# fever_meter_v1.net
KiCad netlist of a schematic drawn in EAGLE
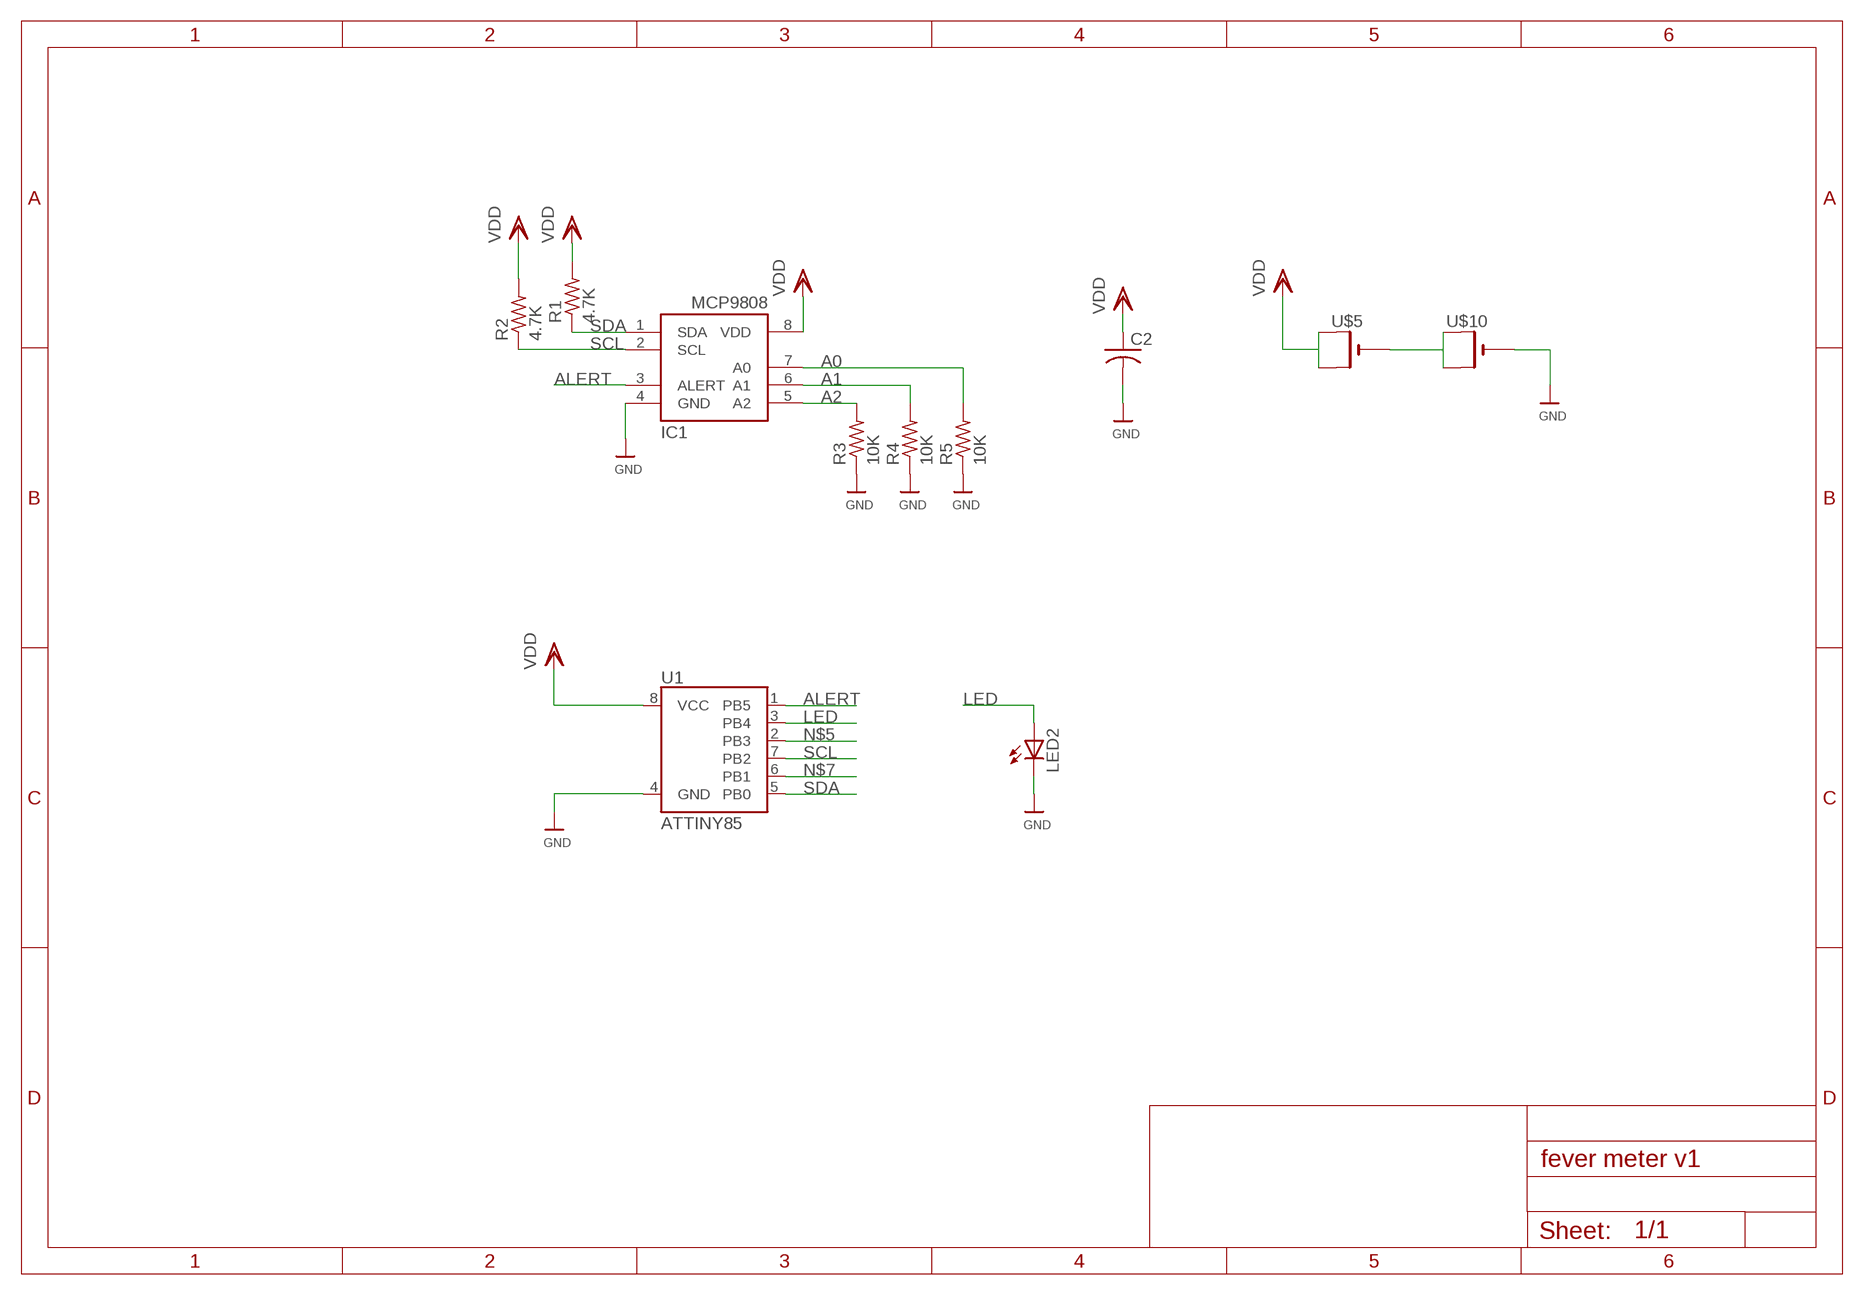
[diagram p0: schematic, sheet 1]

(export (version "E")
  (design (tool "Eeschema 10.0.6"))
  (components
    (comp (ref "C2")
      (value "C-USC1206")
      (footprint "eagle-import:C1206")
      (libsource (lib "eagle-import") (part "C-USC1206"))
    )
    (comp (ref "IC1")
      (value "MCP9808-E/MS")
      (footprint "eagle-import:MSOP8_0.65MM")
      (libsource (lib "eagle-import") (part "MCP9808-E/MS"))
    )
    (comp (ref "LED2")
      (value "LEDSMT1206")
      (footprint "eagle-import:1206")
      (libsource (lib "eagle-import") (part "LEDSMT1206"))
    )
    (comp (ref "R1")
      (value "4.7K")
      (footprint "eagle-import:M1206")
      (libsource (lib "eagle-import") (part "R-US_M1206"))
    )
    (comp (ref "R2")
      (value "4.7K")
      (footprint "eagle-import:M1206")
      (libsource (lib "eagle-import") (part "R-US_M1206"))
    )
    (comp (ref "R3")
      (value "10K")
      (footprint "eagle-import:M1206")
      (libsource (lib "eagle-import") (part "R-US_M1206"))
    )
    (comp (ref "R4")
      (value "10K")
      (footprint "eagle-import:M1206")
      (libsource (lib "eagle-import") (part "R-US_M1206"))
    )
    (comp (ref "R5")
      (value "10K")
      (footprint "eagle-import:M1206")
      (libsource (lib "eagle-import") (part "R-US_M1206"))
    )
    (comp (ref "U$5")
      (value "CR1220SMT")
      (footprint "eagle-import:CR1220-SMD")
      (libsource (lib "eagle-import") (part "CR1220SMT"))
    )
    (comp (ref "U$10")
      (value "CR1220SMT")
      (footprint "eagle-import:CR1220-SMD")
      (libsource (lib "eagle-import") (part "CR1220SMT"))
    )
    (comp (ref "U1")
      (value "ATTINY85")
      (footprint "eagle-import:ATTINY85")
      (libsource (lib "eagle-import") (part "ATTINY85"))
    )
  )
  (nets
    (net (code "1") (name "/A0") (class "Default")
      (node (ref "IC1") (pin "7") (pinfunction "A0_7") (pintype "input"))
      (node (ref "R5") (pin "2") (pinfunction "2_2") (pintype "passive"))
    )
    (net (code "2") (name "/A1") (class "Default")
      (node (ref "IC1") (pin "6") (pinfunction "A1_6") (pintype "input"))
      (node (ref "R4") (pin "2") (pinfunction "2_2") (pintype "passive"))
    )
    (net (code "3") (name "/A2") (class "Default")
      (node (ref "IC1") (pin "5") (pinfunction "A2_5") (pintype "input"))
      (node (ref "R3") (pin "2") (pinfunction "2_2") (pintype "passive"))
    )
    (net (code "4") (name "/ALERT") (class "Default")
      (node (ref "IC1") (pin "3") (pinfunction "ALERT_3") (pintype "open_collector"))
      (node (ref "U1") (pin "1") (pinfunction "PB5_1") (pintype "bidirectional"))
    )
    (net (code "5") (name "/LED") (class "Default")
      (node (ref "LED2") (pin "A") (pinfunction "A_A") (pintype "passive"))
      (node (ref "U1") (pin "3") (pinfunction "PB4_3") (pintype "bidirectional"))
    )
    (net (code "6") (name "/N$5") (class "Default")
      (node (ref "U1") (pin "2") (pinfunction "PB3_2") (pintype "bidirectional"))
    )
    (net (code "7") (name "/N$7") (class "Default")
      (node (ref "U1") (pin "6") (pinfunction "PB1_6") (pintype "bidirectional"))
    )
    (net (code "8") (name "/SCL") (class "Default")
      (node (ref "IC1") (pin "2") (pinfunction "SCL_2") (pintype "bidirectional"))
      (node (ref "R2") (pin "1") (pinfunction "1_1") (pintype "passive"))
      (node (ref "U1") (pin "7") (pinfunction "PB2_7") (pintype "bidirectional"))
    )
    (net (code "9") (name "/SDA") (class "Default")
      (node (ref "IC1") (pin "1") (pinfunction "SDA_1") (pintype "bidirectional"))
      (node (ref "R1") (pin "1") (pinfunction "1_1") (pintype "passive"))
      (node (ref "U1") (pin "5") (pinfunction "PB0_5") (pintype "bidirectional"))
    )
    (net (code "10") (name "GND") (class "Default")
      (node (ref "C2") (pin "2") (pinfunction "2_2") (pintype "passive"))
      (node (ref "IC1") (pin "4") (pinfunction "GND_4") (pintype "power_in"))
      (node (ref "LED2") (pin "C") (pinfunction "C_C") (pintype "passive"))
      (node (ref "R3") (pin "1") (pinfunction "1_1") (pintype "passive"))
      (node (ref "R4") (pin "1") (pinfunction "1_1") (pintype "passive"))
      (node (ref "R5") (pin "1") (pinfunction "1_1") (pintype "passive"))
      (node (ref "U$10") (pin "-") (pinfunction "-_-") (pintype "passive"))
      (node (ref "U1") (pin "4") (pinfunction "GND_4") (pintype "bidirectional"))
    )
    (net (code "11") (name "Net-(U$10-+)") (class "Default")
      (node (ref "U$10") (pin "+$1") (pinfunction "+_+$1") (pintype "passive"))
      (node (ref "U$10") (pin "+$2") (pinfunction "+1_+$2") (pintype "passive"))
      (node (ref "U$5") (pin "-") (pinfunction "-_-") (pintype "passive"))
    )
    (net (code "12") (name "VDD") (class "Default")
      (node (ref "C2") (pin "1") (pinfunction "1_1") (pintype "passive"))
      (node (ref "IC1") (pin "8") (pinfunction "VDD_8") (pintype "power_in"))
      (node (ref "R1") (pin "2") (pinfunction "2_2") (pintype "passive"))
      (node (ref "R2") (pin "2") (pinfunction "2_2") (pintype "passive"))
      (node (ref "U$5") (pin "+$1") (pinfunction "+_+$1") (pintype "passive"))
      (node (ref "U$5") (pin "+$2") (pinfunction "+1_+$2") (pintype "passive"))
      (node (ref "U1") (pin "8") (pinfunction "VCC_8") (pintype "bidirectional"))
    )
  )
)
